# 7-seg.net
KiCad netlist of a schematic drawn in EAGLE
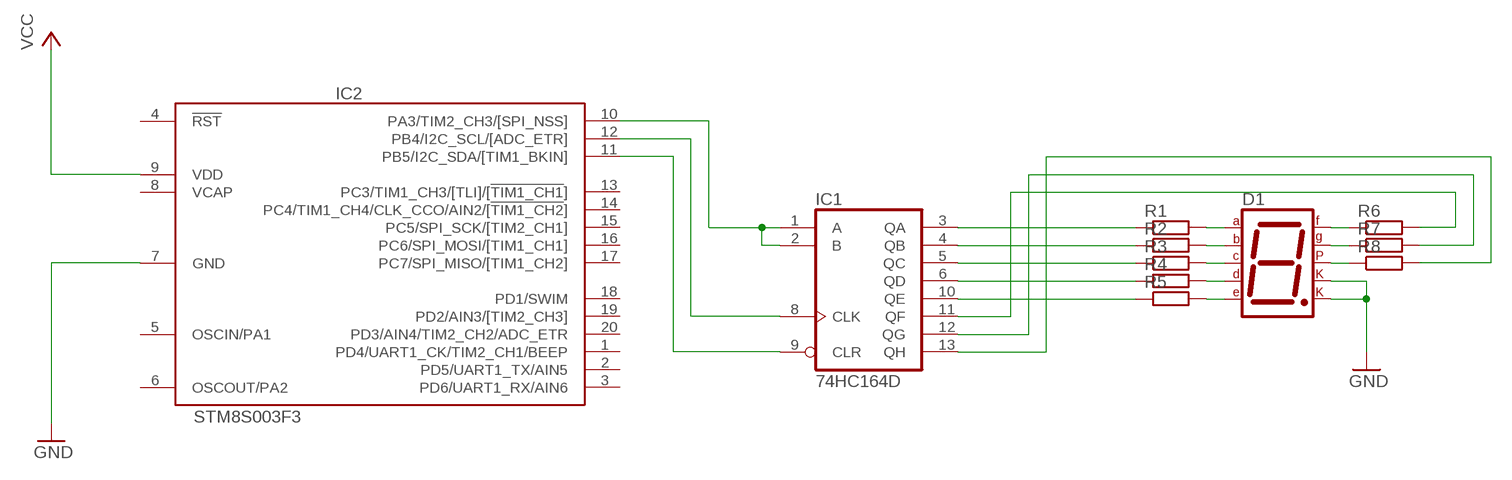
[diagram p0: schematic, sheet 1]

(export (version "E")
  (design (tool "Eeschema 10.0.6"))
  (components
    (comp (ref "D1")
      (value "7SEG-MCK")
      (footprint "eagle-import:7SEG-7")
      (libsource (lib "eagle-import") (part "7SEG-MCK"))
    )
    (comp (ref "IC1")
      (value "74HC164D")
      (footprint "eagle-import:SO14")
      (libsource (lib "eagle-import") (part "74164DHC"))
    )
    (comp (ref "IC2")
      (value "STM8S003F3")
      (footprint "eagle-import:TSSOP20")
      (libsource (lib "eagle-import") (part "STM8S003F3"))
    )
    (comp (ref "R1")
      (value "R-EU_R0805")
      (footprint "eagle-import:R0805")
      (libsource (lib "eagle-import") (part "R-EU_R0805"))
    )
    (comp (ref "R2")
      (value "R-EU_R0805")
      (footprint "eagle-import:R0805")
      (libsource (lib "eagle-import") (part "R-EU_R0805"))
    )
    (comp (ref "R3")
      (value "R-EU_R0805")
      (footprint "eagle-import:R0805")
      (libsource (lib "eagle-import") (part "R-EU_R0805"))
    )
    (comp (ref "R4")
      (value "R-EU_R0805")
      (footprint "eagle-import:R0805")
      (libsource (lib "eagle-import") (part "R-EU_R0805"))
    )
    (comp (ref "R5")
      (value "R-EU_R0805")
      (footprint "eagle-import:R0805")
      (libsource (lib "eagle-import") (part "R-EU_R0805"))
    )
    (comp (ref "R6")
      (value "R-EU_R0805")
      (footprint "eagle-import:R0805")
      (libsource (lib "eagle-import") (part "R-EU_R0805"))
    )
    (comp (ref "R7")
      (value "R-EU_R0805")
      (footprint "eagle-import:R0805")
      (libsource (lib "eagle-import") (part "R-EU_R0805"))
    )
    (comp (ref "R8")
      (value "R-EU_R0805")
      (footprint "eagle-import:R0805")
      (libsource (lib "eagle-import") (part "R-EU_R0805"))
    )
  )
  (nets
    (net (code "1") (name "/VCAP") (class "Default")
      (node (ref "IC2") (pin "8") (pinfunction "VCAP_8") (pintype "power_in"))
    )
    (net (code "2") (name "GND") (class "Default")
      (node (ref "D1") (pin "1") (pinfunction "CK1_1") (pintype "passive"))
      (node (ref "D1") (pin "6") (pinfunction "CK2_6") (pintype "passive"))
      (node (ref "IC2") (pin "7") (pinfunction "GND_7") (pintype "power_in"))
    )
    (net (code "3") (name "Net-(D1-A)") (class "Default")
      (node (ref "D1") (pin "10") (pinfunction "A_10") (pintype "passive"))
      (node (ref "R1") (pin "2") (pinfunction "2_2") (pintype "passive"))
    )
    (net (code "4") (name "Net-(D1-B)") (class "Default")
      (node (ref "D1") (pin "9") (pinfunction "B_9") (pintype "passive"))
      (node (ref "R2") (pin "2") (pinfunction "2_2") (pintype "passive"))
    )
    (net (code "5") (name "Net-(D1-C)") (class "Default")
      (node (ref "D1") (pin "8") (pinfunction "C_8") (pintype "passive"))
      (node (ref "R3") (pin "2") (pinfunction "2_2") (pintype "passive"))
    )
    (net (code "6") (name "Net-(D1-D)") (class "Default")
      (node (ref "D1") (pin "5") (pinfunction "D_5") (pintype "passive"))
      (node (ref "R4") (pin "2") (pinfunction "2_2") (pintype "passive"))
    )
    (net (code "7") (name "Net-(D1-DP)") (class "Default")
      (node (ref "D1") (pin "7") (pinfunction "DP_7") (pintype "passive"))
      (node (ref "R8") (pin "1") (pinfunction "1_1") (pintype "passive"))
    )
    (net (code "8") (name "Net-(D1-E)") (class "Default")
      (node (ref "D1") (pin "4") (pinfunction "E_4") (pintype "passive"))
      (node (ref "R5") (pin "2") (pinfunction "2_2") (pintype "passive"))
    )
    (net (code "9") (name "Net-(D1-F)") (class "Default")
      (node (ref "D1") (pin "2") (pinfunction "F_2") (pintype "passive"))
      (node (ref "R6") (pin "1") (pinfunction "1_1") (pintype "passive"))
    )
    (net (code "10") (name "Net-(D1-G)") (class "Default")
      (node (ref "D1") (pin "3") (pinfunction "G_3") (pintype "passive"))
      (node (ref "R7") (pin "1") (pinfunction "1_1") (pintype "passive"))
    )
    (net (code "11") (name "Net-(IC1A-A)") (class "Default")
      (node (ref "IC1") (pin "1") (pinfunction "A_1") (pintype "input"))
      (node (ref "IC1") (pin "2") (pinfunction "B_2") (pintype "input"))
      (node (ref "IC2") (pin "10") (pinfunction "PA3/TIM2_CH3/[SPI_NSS]_10") (pintype "bidirectional"))
    )
    (net (code "12") (name "Net-(IC1A-CLK)") (class "Default")
      (node (ref "IC1") (pin "8") (pinfunction "CLK_8") (pintype "input"))
      (node (ref "IC2") (pin "12") (pinfunction "PB4/I2C_SCL/[ADC_ETR]_12") (pintype "bidirectional"))
    )
    (net (code "13") (name "Net-(IC1A-CLR)") (class "Default")
      (node (ref "IC1") (pin "9") (pinfunction "CLR_9") (pintype "input"))
      (node (ref "IC2") (pin "11") (pinfunction "PB5/I2C_SDA/[TIM1_BKIN]_11") (pintype "bidirectional"))
    )
    (net (code "14") (name "Net-(IC1A-QA)") (class "Default")
      (node (ref "IC1") (pin "3") (pinfunction "QA_3") (pintype "output"))
      (node (ref "R1") (pin "1") (pinfunction "1_1") (pintype "passive"))
    )
    (net (code "15") (name "Net-(IC1A-QB)") (class "Default")
      (node (ref "IC1") (pin "4") (pinfunction "QB_4") (pintype "output"))
      (node (ref "R2") (pin "1") (pinfunction "1_1") (pintype "passive"))
    )
    (net (code "16") (name "Net-(IC1A-QC)") (class "Default")
      (node (ref "IC1") (pin "5") (pinfunction "QC_5") (pintype "output"))
      (node (ref "R3") (pin "1") (pinfunction "1_1") (pintype "passive"))
    )
    (net (code "17") (name "Net-(IC1A-QD)") (class "Default")
      (node (ref "IC1") (pin "6") (pinfunction "QD_6") (pintype "output"))
      (node (ref "R4") (pin "1") (pinfunction "1_1") (pintype "passive"))
    )
    (net (code "18") (name "Net-(IC1A-QE)") (class "Default")
      (node (ref "IC1") (pin "10") (pinfunction "QE_10") (pintype "output"))
      (node (ref "R5") (pin "1") (pinfunction "1_1") (pintype "passive"))
    )
    (net (code "19") (name "Net-(IC1A-QF)") (class "Default")
      (node (ref "IC1") (pin "11") (pinfunction "QF_11") (pintype "output"))
      (node (ref "R6") (pin "2") (pinfunction "2_2") (pintype "passive"))
    )
    (net (code "20") (name "Net-(IC1A-QG)") (class "Default")
      (node (ref "IC1") (pin "12") (pinfunction "QG_12") (pintype "output"))
      (node (ref "R7") (pin "2") (pinfunction "2_2") (pintype "passive"))
    )
    (net (code "21") (name "Net-(IC1A-QH)") (class "Default")
      (node (ref "IC1") (pin "13") (pinfunction "QH_13") (pintype "output"))
      (node (ref "R8") (pin "2") (pinfunction "2_2") (pintype "passive"))
    )
    (net (code "22") (name "VCC") (class "Default")
      (node (ref "IC2") (pin "9") (pinfunction "VDD_9") (pintype "power_in"))
    )
    (net (code "23") (name "unconnected-(IC2-OSCIN{slash}PA1-Pad5)") (class "Default")
      (node (ref "IC2") (pin "5") (pinfunction "OSCIN/PA1_5") (pintype "bidirectional"))
    )
    (net (code "24") (name "unconnected-(IC2-OSCOUT{slash}PA2-Pad6)") (class "Default")
      (node (ref "IC2") (pin "6") (pinfunction "OSCOUT/PA2_6") (pintype "bidirectional"))
    )
    (net (code "25") (name "unconnected-(IC2-PC3{slash}TIM1_CH3{slash}[TLI]{slash}[~{TIM1_CH1}]-Pad13)") (class "Default")
      (node (ref "IC2") (pin "13") (pinfunction "PC3/TIM1_CH3/[TLI]/[~{TIM1_CH1}]_13") (pintype "bidirectional"))
    )
    (net (code "26") (name "unconnected-(IC2-PC4{slash}TIM1_CH4{slash}CLK_CCO{slash}AIN2{slash}[~{TIM1_CH2}]-Pad14)") (class "Default")
      (node (ref "IC2") (pin "14") (pinfunction "PC4/TIM1_CH4/CLK_CCO/AIN2/[~{TIM1_CH2}]_14") (pintype "bidirectional"))
    )
    (net (code "27") (name "unconnected-(IC2-PC5{slash}SPI_SCK{slash}[TIM2_CH1]-Pad15)") (class "Default")
      (node (ref "IC2") (pin "15") (pinfunction "PC5/SPI_SCK/[TIM2_CH1]_15") (pintype "bidirectional"))
    )
    (net (code "28") (name "unconnected-(IC2-PC6{slash}SPI_MOSI{slash}[TIM1_CH1]-Pad16)") (class "Default")
      (node (ref "IC2") (pin "16") (pinfunction "PC6/SPI_MOSI/[TIM1_CH1]_16") (pintype "bidirectional"))
    )
    (net (code "29") (name "unconnected-(IC2-PC7{slash}SPI_MISO{slash}[TIM1_CH2]-Pad17)") (class "Default")
      (node (ref "IC2") (pin "17") (pinfunction "PC7/SPI_MISO/[TIM1_CH2]_17") (pintype "bidirectional"))
    )
    (net (code "30") (name "unconnected-(IC2-PD1{slash}SWIM-Pad18)") (class "Default")
      (node (ref "IC2") (pin "18") (pinfunction "PD1/SWIM_18") (pintype "bidirectional"))
    )
    (net (code "31") (name "unconnected-(IC2-PD2{slash}AIN3{slash}[TIM2_CH3]-Pad19)") (class "Default")
      (node (ref "IC2") (pin "19") (pinfunction "PD2/AIN3/[TIM2_CH3]_19") (pintype "bidirectional"))
    )
    (net (code "32") (name "unconnected-(IC2-PD3{slash}AIN4{slash}TIM2_CH2{slash}ADC_ETR-Pad20)") (class "Default")
      (node (ref "IC2") (pin "20") (pinfunction "PD3/AIN4/TIM2_CH2/ADC_ETR_20") (pintype "bidirectional"))
    )
    (net (code "33") (name "unconnected-(IC2-PD4{slash}UART1_CK{slash}TIM2_CH1{slash}BEEP-Pad1)") (class "Default")
      (node (ref "IC2") (pin "1") (pinfunction "PD4/UART1_CK/TIM2_CH1/BEEP_1") (pintype "bidirectional"))
    )
    (net (code "34") (name "unconnected-(IC2-PD5{slash}UART1_TX{slash}AIN5-Pad2)") (class "Default")
      (node (ref "IC2") (pin "2") (pinfunction "PD5/UART1_TX/AIN5_2") (pintype "bidirectional"))
    )
    (net (code "35") (name "unconnected-(IC2-PD6{slash}UART1_RX{slash}AIN6-Pad3)") (class "Default")
      (node (ref "IC2") (pin "3") (pinfunction "PD6/UART1_RX/AIN6_3") (pintype "bidirectional"))
    )
    (net (code "36") (name "unconnected-(IC2-~{RST}-Pad4)") (class "Default")
      (node (ref "IC2") (pin "4") (pinfunction "~{RST}_4") (pintype "input"))
    )
  )
)
